# INTERFACE.net
KiCad netlist of a schematic drawn in Altium Designer
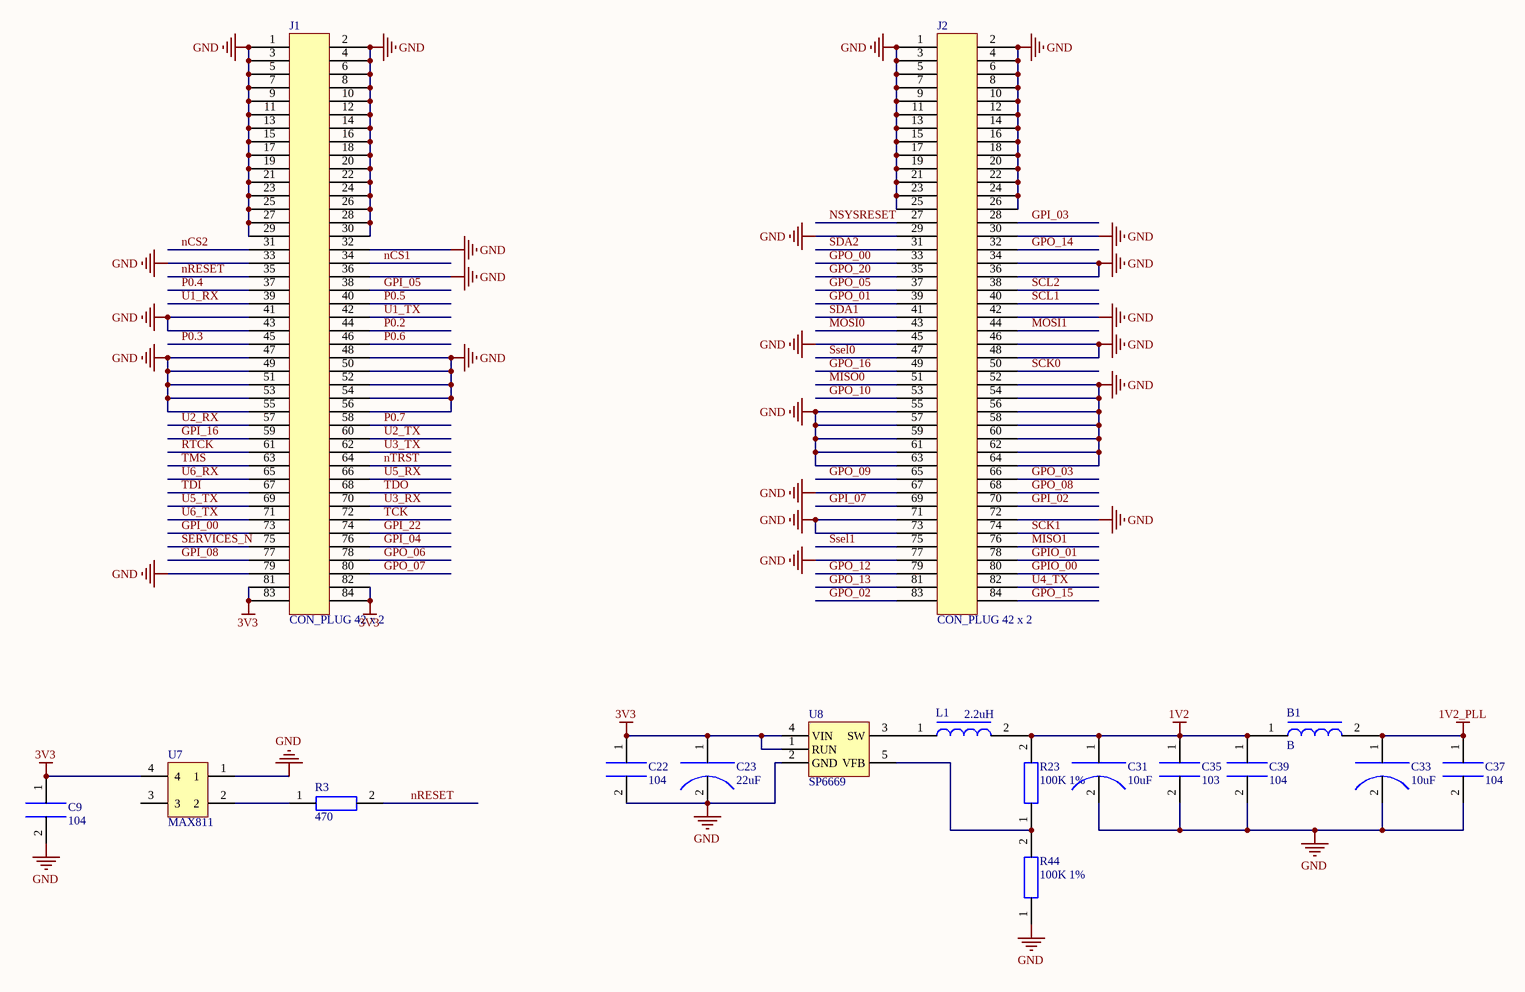
[diagram p0: INTERFACE.SchDoc]

(export (version "E")
  (design (tool "Eeschema 10.0.6"))
  (components
    (comp (ref "B1") (value "B") (footprint "0603") (libsource (lib "MyProject1") (part "B")))
    (comp (ref "C9") (value "104") (footprint "0603C") (libsource (lib "MyProject1") (part "CAP")))
    (comp (ref "C22") (value "104") (footprint "0603C") (libsource (lib "MyProject1") (part "CAP")))
    (comp (ref "C23") (value "22uF") (footprint "TC-3528") (libsource (lib "MyProject1") (part "CAP_1")))
    (comp (ref "C31") (value "10uF") (footprint "TC-3528") (libsource (lib "MyProject1") (part "CAP_1")))
    (comp (ref "C33") (value "10uF") (footprint "TC-3528") (libsource (lib "MyProject1") (part "CAP_1")))
    (comp (ref "C35") (value "103") (footprint "0603C") (libsource (lib "MyProject1") (part "CAP")))
    (comp (ref "C37") (value "104") (footprint "0603C") (libsource (lib "MyProject1") (part "CAP")))
    (comp (ref "C39") (value "104") (footprint "0603C") (libsource (lib "MyProject1") (part "CAP")))
    (comp (ref "J1")
      (value "CON_PLUG 42 x 2")
      (footprint "DIP84")
      (libsource (lib "MyProject1") (part "CON_PLUG 42 x 2"))
    )
    (comp (ref "J2")
      (value "CON_PLUG 42 x 2")
      (footprint "DIP84")
      (libsource (lib "MyProject1") (part "CON_PLUG 42 x 2"))
    )
    (comp (ref "L1") (value "2.2uH") (footprint "0805") (libsource (lib "MyProject1") (part "INDUCTOR")))
    (comp (ref "R3") (value "470") (footprint "0603R") (libsource (lib "MyProject1") (part "RES")))
    (comp (ref "R23") (value "100K 1%") (footprint "0603R") (libsource (lib "MyProject1") (part "RES")))
    (comp (ref "R44") (value "100K 1%") (footprint "0603R") (libsource (lib "MyProject1") (part "RES")))
    (comp (ref "U7") (value "MAX811") (footprint "MAX811") (libsource (lib "MyProject1") (part "MAX811")))
    (comp (ref "U8") (value "SP6669") (footprint "SOT-23-5") (libsource (lib "MyProject1") (part "SP6669")))
  )
  (nets
    (net (code "1") (name "/GPIO_00") (class "Default") (node (ref "J2") (pin "80") (pintype "passive")))
    (net (code "2") (name "/GPIO_01") (class "Default") (node (ref "J2") (pin "78") (pintype "passive")))
    (net (code "3") (name "/GPI_00") (class "Default") (node (ref "J1") (pin "73") (pintype "passive")))
    (net (code "4") (name "/GPI_02") (class "Default") (node (ref "J2") (pin "70") (pintype "passive")))
    (net (code "5") (name "/GPI_03") (class "Default") (node (ref "J2") (pin "28") (pintype "passive")))
    (net (code "6") (name "/GPI_04") (class "Default") (node (ref "J1") (pin "76") (pintype "passive")))
    (net (code "7") (name "/GPI_05") (class "Default") (node (ref "J1") (pin "38") (pintype "passive")))
    (net (code "8") (name "/GPI_07") (class "Default") (node (ref "J2") (pin "69") (pintype "passive")))
    (net (code "9") (name "/GPI_08") (class "Default") (node (ref "J1") (pin "77") (pintype "passive")))
    (net (code "10") (name "/GPI_16") (class "Default") (node (ref "J1") (pin "59") (pintype "passive")))
    (net (code "11") (name "/GPI_22") (class "Default") (node (ref "J1") (pin "74") (pintype "passive")))
    (net (code "12") (name "/GPO_00") (class "Default") (node (ref "J2") (pin "33") (pintype "passive")))
    (net (code "13") (name "/GPO_01") (class "Default") (node (ref "J2") (pin "39") (pintype "passive")))
    (net (code "14") (name "/GPO_02") (class "Default") (node (ref "J2") (pin "83") (pintype "passive")))
    (net (code "15") (name "/GPO_03") (class "Default") (node (ref "J2") (pin "66") (pintype "passive")))
    (net (code "16") (name "/GPO_05") (class "Default") (node (ref "J2") (pin "37") (pintype "passive")))
    (net (code "17") (name "/GPO_06") (class "Default") (node (ref "J1") (pin "78") (pintype "passive")))
    (net (code "18") (name "/GPO_07") (class "Default") (node (ref "J1") (pin "80") (pintype "passive")))
    (net (code "19") (name "/GPO_08") (class "Default") (node (ref "J2") (pin "68") (pintype "passive")))
    (net (code "20") (name "/GPO_09") (class "Default") (node (ref "J2") (pin "65") (pintype "passive")))
    (net (code "21") (name "/GPO_10") (class "Default") (node (ref "J2") (pin "53") (pintype "passive")))
    (net (code "22") (name "/GPO_12") (class "Default") (node (ref "J2") (pin "79") (pintype "passive")))
    (net (code "23") (name "/GPO_13") (class "Default") (node (ref "J2") (pin "81") (pintype "passive")))
    (net (code "24") (name "/GPO_14") (class "Default") (node (ref "J2") (pin "32") (pintype "passive")))
    (net (code "25") (name "/GPO_15") (class "Default") (node (ref "J2") (pin "84") (pintype "passive")))
    (net (code "26") (name "/GPO_16") (class "Default") (node (ref "J2") (pin "49") (pintype "passive")))
    (net (code "27") (name "/GPO_20") (class "Default") (node (ref "J2") (pin "35") (pintype "passive")))
    (net (code "28") (name "/MISO0") (class "Default") (node (ref "J2") (pin "51") (pintype "passive")))
    (net (code "29") (name "/MISO1") (class "Default") (node (ref "J2") (pin "76") (pintype "passive")))
    (net (code "30") (name "/MOSI0") (class "Default") (node (ref "J2") (pin "43") (pintype "passive")))
    (net (code "31") (name "/MOSI1") (class "Default") (node (ref "J2") (pin "44") (pintype "passive")))
    (net (code "32") (name "/NSYSRESET") (class "Default") (node (ref "J2") (pin "27") (pintype "passive")))
    (net (code "33") (name "/P0.2") (class "Default") (node (ref "J1") (pin "44") (pintype "passive")))
    (net (code "34") (name "/P0.3") (class "Default") (node (ref "J1") (pin "45") (pintype "passive")))
    (net (code "35") (name "/P0.4") (class "Default") (node (ref "J1") (pin "37") (pintype "passive")))
    (net (code "36") (name "/P0.5") (class "Default") (node (ref "J1") (pin "40") (pintype "passive")))
    (net (code "37") (name "/P0.6") (class "Default") (node (ref "J1") (pin "46") (pintype "passive")))
    (net (code "38") (name "/P0.7") (class "Default") (node (ref "J1") (pin "58") (pintype "passive")))
    (net (code "39") (name "/RTCK") (class "Default") (node (ref "J1") (pin "61") (pintype "passive")))
    (net (code "40") (name "/SCK0") (class "Default") (node (ref "J2") (pin "50") (pintype "passive")))
    (net (code "41") (name "/SCK1") (class "Default") (node (ref "J2") (pin "74") (pintype "passive")))
    (net (code "42") (name "/SCL1") (class "Default") (node (ref "J2") (pin "40") (pintype "passive")))
    (net (code "43") (name "/SCL2") (class "Default") (node (ref "J2") (pin "38") (pintype "passive")))
    (net (code "44") (name "/SDA1") (class "Default") (node (ref "J2") (pin "41") (pintype "passive")))
    (net (code "45") (name "/SDA2") (class "Default") (node (ref "J2") (pin "31") (pintype "passive")))
    (net (code "46") (name "/SERVICES_N") (class "Default") (node (ref "J1") (pin "75") (pintype "passive")))
    (net (code "47") (name "/Ssel0") (class "Default") (node (ref "J2") (pin "47") (pintype "passive")))
    (net (code "48") (name "/Ssel1") (class "Default") (node (ref "J2") (pin "75") (pintype "passive")))
    (net (code "49") (name "/TCK") (class "Default") (node (ref "J1") (pin "72") (pintype "passive")))
    (net (code "50") (name "/TDI") (class "Default") (node (ref "J1") (pin "67") (pintype "passive")))
    (net (code "51") (name "/TDO") (class "Default") (node (ref "J1") (pin "68") (pintype "passive")))
    (net (code "52") (name "/TMS") (class "Default") (node (ref "J1") (pin "63") (pintype "passive")))
    (net (code "53") (name "/U1_RX") (class "Default") (node (ref "J1") (pin "39") (pintype "passive")))
    (net (code "54") (name "/U1_TX") (class "Default") (node (ref "J1") (pin "42") (pintype "passive")))
    (net (code "55") (name "/U2_RX") (class "Default") (node (ref "J1") (pin "57") (pintype "passive")))
    (net (code "56") (name "/U2_TX") (class "Default") (node (ref "J1") (pin "60") (pintype "passive")))
    (net (code "57") (name "/U3_RX") (class "Default") (node (ref "J1") (pin "70") (pintype "passive")))
    (net (code "58") (name "/U3_TX") (class "Default") (node (ref "J1") (pin "62") (pintype "passive")))
    (net (code "59") (name "/U4_TX") (class "Default") (node (ref "J2") (pin "82") (pintype "passive")))
    (net (code "60") (name "/U5_RX") (class "Default") (node (ref "J1") (pin "66") (pintype "passive")))
    (net (code "61") (name "/U5_TX") (class "Default") (node (ref "J1") (pin "69") (pintype "passive")))
    (net (code "62") (name "/U6_RX") (class "Default") (node (ref "J1") (pin "65") (pintype "passive")))
    (net (code "63") (name "/U6_TX") (class "Default") (node (ref "J1") (pin "71") (pintype "passive")))
    (net (code "64") (name "/nCS1") (class "Default") (node (ref "J1") (pin "34") (pintype "passive")))
    (net (code "65") (name "/nCS2") (class "Default") (node (ref "J1") (pin "31") (pintype "passive")))
    (net (code "66") (name "/nRESET") (class "Default")
      (node (ref "J1") (pin "35") (pintype "passive"))
      (node (ref "R3") (pin "2") (pinfunction "2_2") (pintype "passive"))
    )
    (net (code "67") (name "/nTRST") (class "Default") (node (ref "J1") (pin "64") (pintype "passive")))
    (net (code "68") (name "1V2") (class "Default")
      (node (ref "B1") (pin "1") (pinfunction "1_1") (pintype "passive"))
      (node (ref "C31") (pin "1") (pinfunction "1_1") (pintype "passive"))
      (node (ref "C35") (pin "1") (pinfunction "1_1") (pintype "passive"))
      (node (ref "C39") (pin "1") (pinfunction "1_1") (pintype "passive"))
      (node (ref "L1") (pin "2") (pinfunction "2_2") (pintype "passive"))
      (node (ref "R23") (pin "2") (pinfunction "2_2") (pintype "passive"))
    )
    (net (code "69") (name "1V2_PLL") (class "Default")
      (node (ref "B1") (pin "2") (pinfunction "2_2") (pintype "passive"))
      (node (ref "C33") (pin "1") (pinfunction "1_1") (pintype "passive"))
      (node (ref "C37") (pin "1") (pinfunction "1_1") (pintype "passive"))
    )
    (net (code "70") (name "3V3") (class "Default")
      (node (ref "C22") (pin "1") (pinfunction "1_1") (pintype "passive"))
      (node (ref "C23") (pin "1") (pinfunction "1_1") (pintype "passive"))
      (node (ref "C9") (pin "1") (pinfunction "1_1") (pintype "passive"))
      (node (ref "J1") (pin "81") (pintype "passive"))
      (node (ref "J1") (pin "82") (pintype "passive"))
      (node (ref "J1") (pin "83") (pintype "passive"))
      (node (ref "J1") (pin "84") (pintype "passive"))
      (node (ref "U7") (pin "4") (pinfunction "4_4") (pintype "passive"))
      (node (ref "U8") (pin "1") (pinfunction "RUN_1") (pintype "passive"))
      (node (ref "U8") (pin "4") (pinfunction "VIN_4") (pintype "passive"))
    )
    (net (code "71") (name "GND") (class "Default")
      (node (ref "C22") (pin "2") (pinfunction "2_2") (pintype "passive"))
      (node (ref "C23") (pin "2") (pinfunction "2_2") (pintype "passive"))
      (node (ref "C31") (pin "2") (pinfunction "2_2") (pintype "passive"))
      (node (ref "C33") (pin "2") (pinfunction "2_2") (pintype "passive"))
      (node (ref "C35") (pin "2") (pinfunction "2_2") (pintype "passive"))
      (node (ref "C37") (pin "2") (pinfunction "2_2") (pintype "passive"))
      (node (ref "C39") (pin "2") (pinfunction "2_2") (pintype "passive"))
      (node (ref "C9") (pin "2") (pinfunction "2_2") (pintype "passive"))
      (node (ref "J1") (pin "1") (pintype "passive"))
      (node (ref "J1") (pin "10") (pintype "passive"))
      (node (ref "J1") (pin "11") (pintype "passive"))
      (node (ref "J1") (pin "12") (pintype "passive"))
      (node (ref "J1") (pin "13") (pintype "passive"))
      (node (ref "J1") (pin "14") (pintype "passive"))
      (node (ref "J1") (pin "15") (pintype "passive"))
      (node (ref "J1") (pin "16") (pintype "passive"))
      (node (ref "J1") (pin "17") (pintype "passive"))
      (node (ref "J1") (pin "18") (pintype "passive"))
      (node (ref "J1") (pin "19") (pintype "passive"))
      (node (ref "J1") (pin "2") (pintype "passive"))
      (node (ref "J1") (pin "20") (pintype "passive"))
      (node (ref "J1") (pin "21") (pintype "passive"))
      (node (ref "J1") (pin "22") (pintype "passive"))
      (node (ref "J1") (pin "23") (pintype "passive"))
      (node (ref "J1") (pin "24") (pintype "passive"))
      (node (ref "J1") (pin "25") (pintype "passive"))
      (node (ref "J1") (pin "26") (pintype "passive"))
      (node (ref "J1") (pin "27") (pintype "passive"))
      (node (ref "J1") (pin "28") (pintype "passive"))
      (node (ref "J1") (pin "29") (pintype "passive"))
      (node (ref "J1") (pin "3") (pintype "passive"))
      (node (ref "J1") (pin "30") (pintype "passive"))
      (node (ref "J1") (pin "32") (pintype "passive"))
      (node (ref "J1") (pin "33") (pintype "passive"))
      (node (ref "J1") (pin "36") (pintype "passive"))
      (node (ref "J1") (pin "4") (pintype "passive"))
      (node (ref "J1") (pin "41") (pintype "passive"))
      (node (ref "J1") (pin "43") (pintype "passive"))
      (node (ref "J1") (pin "47") (pintype "passive"))
      (node (ref "J1") (pin "48") (pintype "passive"))
      (node (ref "J1") (pin "49") (pintype "passive"))
      (node (ref "J1") (pin "5") (pintype "passive"))
      (node (ref "J1") (pin "50") (pintype "passive"))
      (node (ref "J1") (pin "51") (pintype "passive"))
      (node (ref "J1") (pin "52") (pintype "passive"))
      (node (ref "J1") (pin "53") (pintype "passive"))
      (node (ref "J1") (pin "54") (pintype "passive"))
      (node (ref "J1") (pin "55") (pintype "passive"))
      (node (ref "J1") (pin "56") (pintype "passive"))
      (node (ref "J1") (pin "6") (pintype "passive"))
      (node (ref "J1") (pin "7") (pintype "passive"))
      (node (ref "J1") (pin "79") (pintype "passive"))
      (node (ref "J1") (pin "8") (pintype "passive"))
      (node (ref "J1") (pin "9") (pintype "passive"))
      (node (ref "J2") (pin "1") (pintype "passive"))
      (node (ref "J2") (pin "10") (pintype "passive"))
      (node (ref "J2") (pin "11") (pintype "passive"))
      (node (ref "J2") (pin "12") (pintype "passive"))
      (node (ref "J2") (pin "13") (pintype "passive"))
      (node (ref "J2") (pin "14") (pintype "passive"))
      (node (ref "J2") (pin "15") (pintype "passive"))
      (node (ref "J2") (pin "16") (pintype "passive"))
      (node (ref "J2") (pin "17") (pintype "passive"))
      (node (ref "J2") (pin "18") (pintype "passive"))
      (node (ref "J2") (pin "19") (pintype "passive"))
      (node (ref "J2") (pin "2") (pintype "passive"))
      (node (ref "J2") (pin "20") (pintype "passive"))
      (node (ref "J2") (pin "21") (pintype "passive"))
      (node (ref "J2") (pin "22") (pintype "passive"))
      (node (ref "J2") (pin "23") (pintype "passive"))
      (node (ref "J2") (pin "24") (pintype "passive"))
      (node (ref "J2") (pin "25") (pintype "passive"))
      (node (ref "J2") (pin "26") (pintype "passive"))
      (node (ref "J2") (pin "29") (pintype "passive"))
      (node (ref "J2") (pin "3") (pintype "passive"))
      (node (ref "J2") (pin "30") (pintype "passive"))
      (node (ref "J2") (pin "34") (pintype "passive"))
      (node (ref "J2") (pin "36") (pintype "passive"))
      (node (ref "J2") (pin "4") (pintype "passive"))
      (node (ref "J2") (pin "42") (pintype "passive"))
      (node (ref "J2") (pin "45") (pintype "passive"))
      (node (ref "J2") (pin "46") (pintype "passive"))
      (node (ref "J2") (pin "48") (pintype "passive"))
      (node (ref "J2") (pin "5") (pintype "passive"))
      (node (ref "J2") (pin "52") (pintype "passive"))
      (node (ref "J2") (pin "54") (pintype "passive"))
      (node (ref "J2") (pin "55") (pintype "passive"))
      (node (ref "J2") (pin "56") (pintype "passive"))
      (node (ref "J2") (pin "57") (pintype "passive"))
      (node (ref "J2") (pin "58") (pintype "passive"))
      (node (ref "J2") (pin "59") (pintype "passive"))
      (node (ref "J2") (pin "6") (pintype "passive"))
      (node (ref "J2") (pin "60") (pintype "passive"))
      (node (ref "J2") (pin "61") (pintype "passive"))
      (node (ref "J2") (pin "62") (pintype "passive"))
      (node (ref "J2") (pin "63") (pintype "passive"))
      (node (ref "J2") (pin "64") (pintype "passive"))
      (node (ref "J2") (pin "67") (pintype "passive"))
      (node (ref "J2") (pin "7") (pintype "passive"))
      (node (ref "J2") (pin "71") (pintype "passive"))
      (node (ref "J2") (pin "72") (pintype "passive"))
      (node (ref "J2") (pin "73") (pintype "passive"))
      (node (ref "J2") (pin "77") (pintype "passive"))
      (node (ref "J2") (pin "8") (pintype "passive"))
      (node (ref "J2") (pin "9") (pintype "passive"))
      (node (ref "R44") (pin "1") (pinfunction "1_1") (pintype "passive"))
      (node (ref "U7") (pin "1") (pinfunction "1_1") (pintype "passive"))
      (node (ref "U8") (pin "2") (pinfunction "GND_2") (pintype "passive"))
    )
    (net (code "72") (name "Net-(R3-Pad1)") (class "Default")
      (node (ref "R3") (pin "1") (pinfunction "1_1") (pintype "passive"))
      (node (ref "U7") (pin "2") (pinfunction "2_2") (pintype "passive"))
    )
    (net (code "73") (name "Net-(U8-SW)") (class "Default")
      (node (ref "L1") (pin "1") (pinfunction "1_1") (pintype "passive"))
      (node (ref "U8") (pin "3") (pinfunction "SW_3") (pintype "passive"))
    )
    (net (code "74") (name "Net-(U8-VFB)") (class "Default")
      (node (ref "R23") (pin "1") (pinfunction "1_1") (pintype "passive"))
      (node (ref "R44") (pin "2") (pinfunction "2_2") (pintype "passive"))
      (node (ref "U8") (pin "5") (pinfunction "VFB_5") (pintype "passive"))
    )
    (net (code "75") (name "unconnected-(U7-Pad3)") (class "Default")
      (node (ref "U7") (pin "3") (pinfunction "3_3") (pintype "passive"))
    )
  )
)
